# EEG_2.net
KiCad netlist of a schematic drawn in Altium Designer
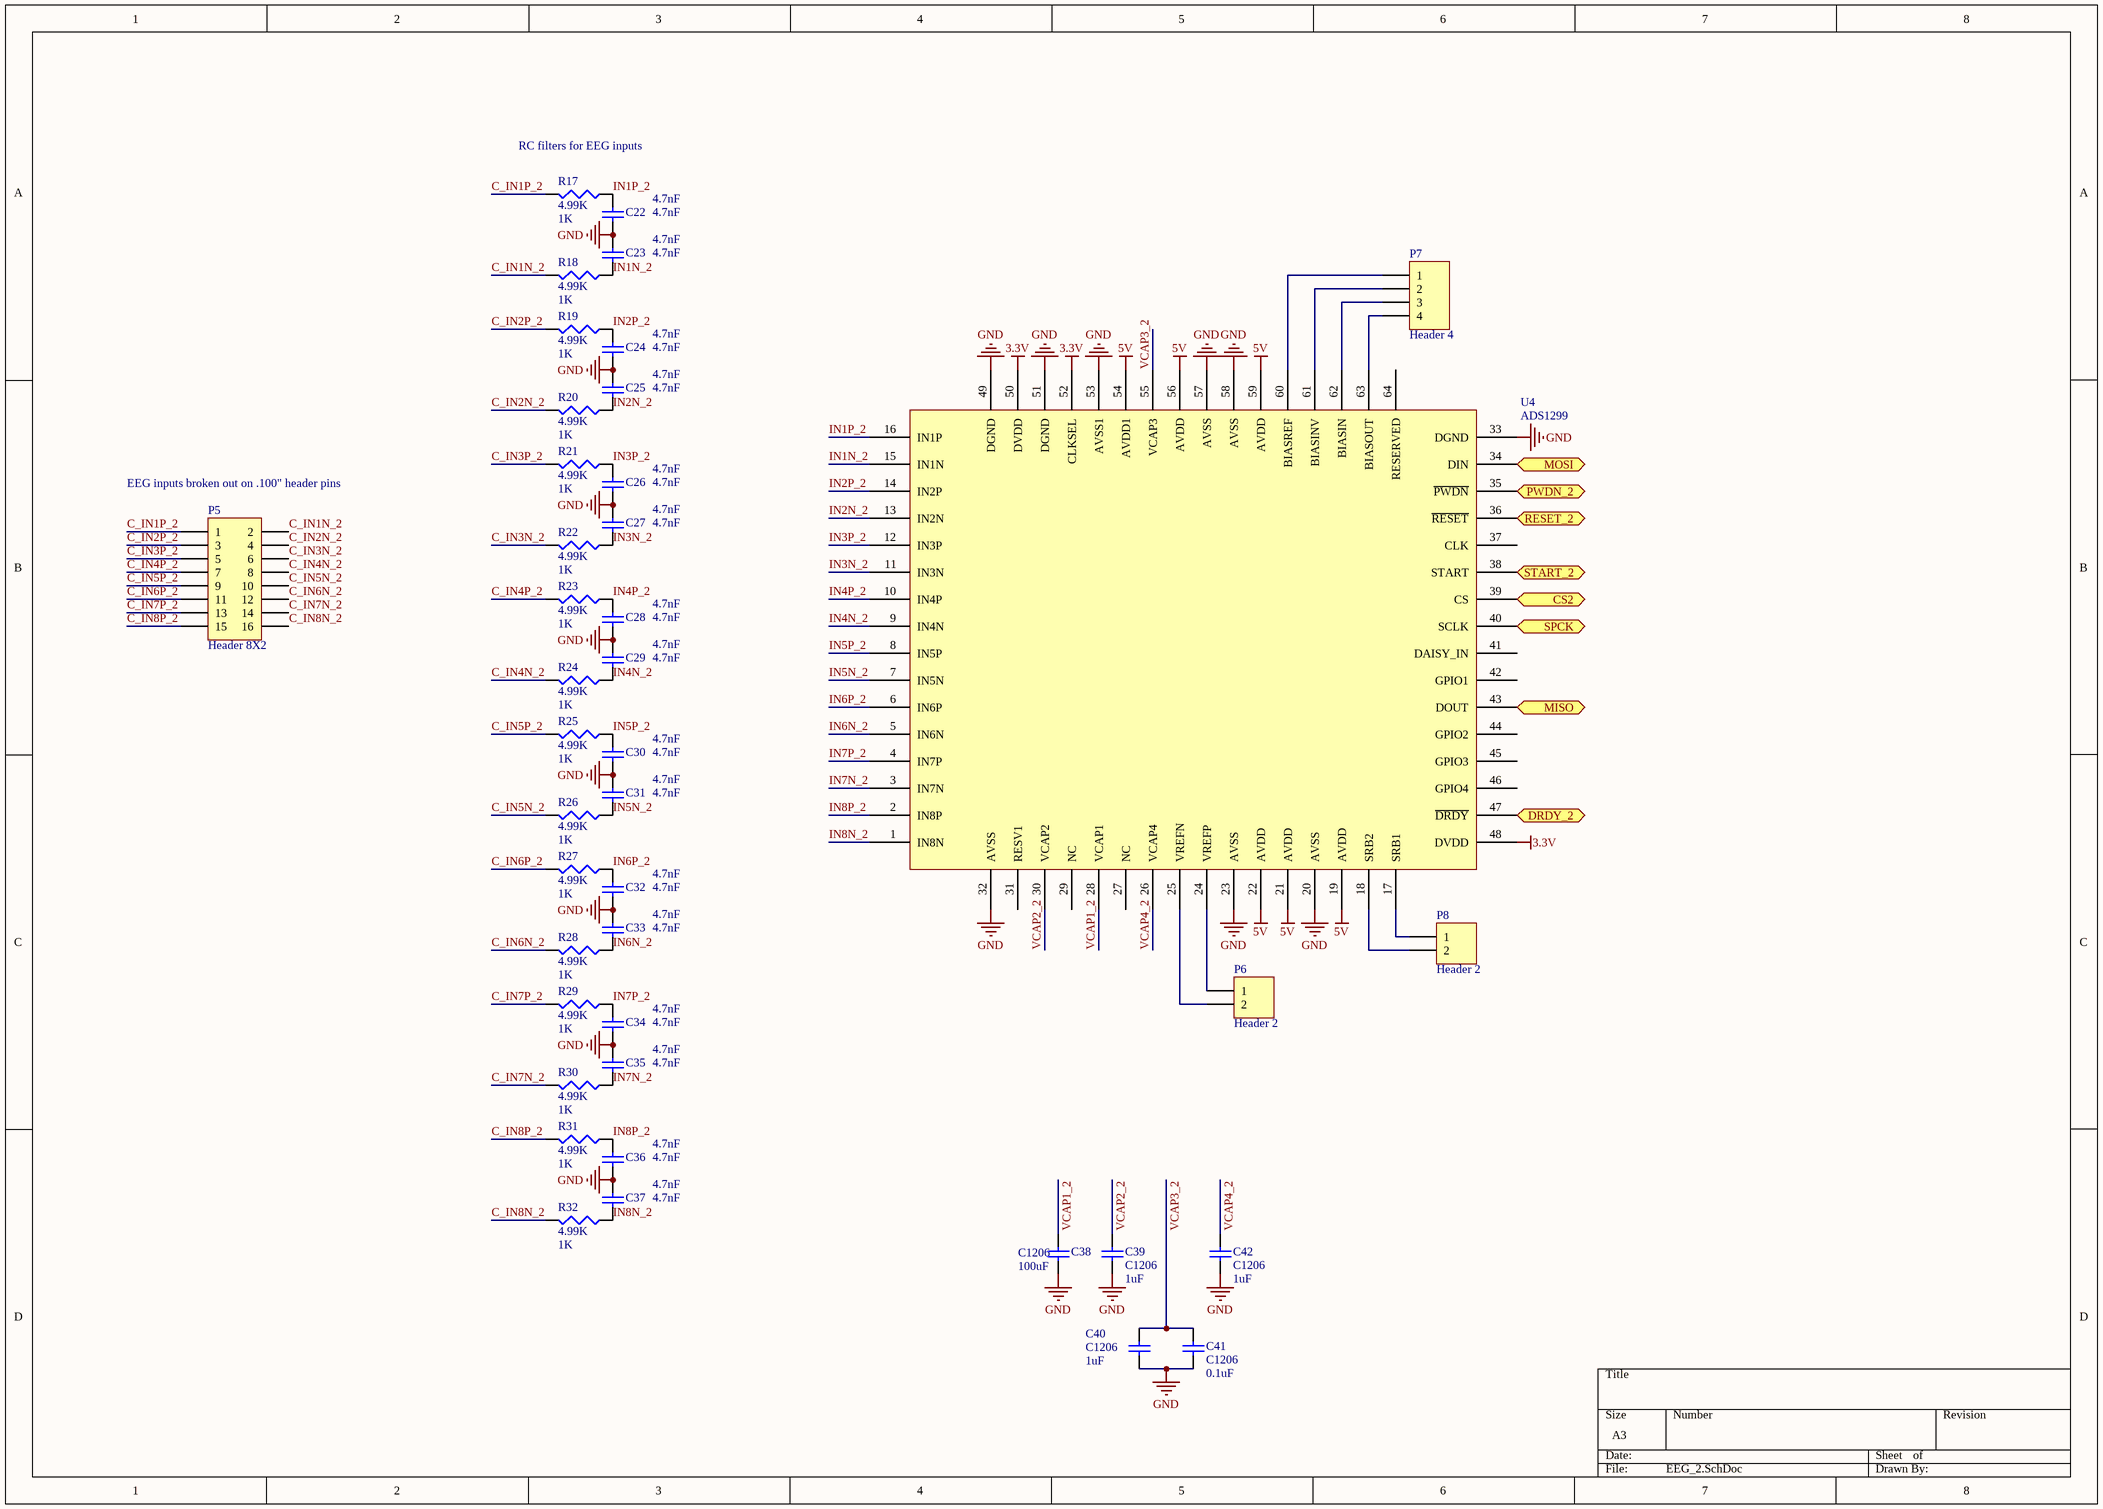
[diagram p0: EEG_2.SchDoc]

(export (version "E")
  (design (tool "Eeschema 10.0.6"))
  (components
    (comp (ref "C22")
      (value "4.7nF")
      (footprint "1608[0603]")
      (description "Capacitor (Semiconductor SIM Model)")
      (fields (field (name "ALTIUM_VALUE") "4.7nF") (field (name "PUBLISHER") "Altium Limited"))
      (libsource (lib "Miscellaneous Devices") (part "Cap Semi"))
    )
    (comp (ref "C23")
      (value "4.7nF")
      (footprint "1608[0603]")
      (description "Capacitor (Semiconductor SIM Model)")
      (fields (field (name "ALTIUM_VALUE") "4.7nF") (field (name "PUBLISHER") "Altium Limited"))
      (libsource (lib "Miscellaneous Devices") (part "Cap Semi"))
    )
    (comp (ref "C24")
      (value "4.7nF")
      (footprint "1608[0603]")
      (description "Capacitor (Semiconductor SIM Model)")
      (fields (field (name "ALTIUM_VALUE") "4.7nF") (field (name "PUBLISHER") "Altium Limited"))
      (libsource (lib "Miscellaneous Devices") (part "Cap Semi"))
    )
    (comp (ref "C25")
      (value "4.7nF")
      (footprint "1608[0603]")
      (description "Capacitor (Semiconductor SIM Model)")
      (fields (field (name "ALTIUM_VALUE") "4.7nF") (field (name "PUBLISHER") "Altium Limited"))
      (libsource (lib "Miscellaneous Devices") (part "Cap Semi"))
    )
    (comp (ref "C26")
      (value "4.7nF")
      (footprint "1608[0603]")
      (description "Capacitor (Semiconductor SIM Model)")
      (fields (field (name "ALTIUM_VALUE") "4.7nF") (field (name "PUBLISHER") "Altium Limited"))
      (libsource (lib "Miscellaneous Devices") (part "Cap Semi"))
    )
    (comp (ref "C27")
      (value "4.7nF")
      (footprint "1608[0603]")
      (description "Capacitor (Semiconductor SIM Model)")
      (fields (field (name "ALTIUM_VALUE") "4.7nF") (field (name "PUBLISHER") "Altium Limited"))
      (libsource (lib "Miscellaneous Devices") (part "Cap Semi"))
    )
    (comp (ref "C28")
      (value "4.7nF")
      (footprint "1608[0603]")
      (description "Capacitor (Semiconductor SIM Model)")
      (fields (field (name "ALTIUM_VALUE") "4.7nF") (field (name "PUBLISHER") "Altium Limited"))
      (libsource (lib "Miscellaneous Devices") (part "Cap Semi"))
    )
    (comp (ref "C29")
      (value "4.7nF")
      (footprint "1608[0603]")
      (description "Capacitor (Semiconductor SIM Model)")
      (fields (field (name "ALTIUM_VALUE") "4.7nF") (field (name "PUBLISHER") "Altium Limited"))
      (libsource (lib "Miscellaneous Devices") (part "Cap Semi"))
    )
    (comp (ref "C30")
      (value "4.7nF")
      (footprint "1608[0603]")
      (description "Capacitor (Semiconductor SIM Model)")
      (fields (field (name "ALTIUM_VALUE") "4.7nF") (field (name "PUBLISHER") "Altium Limited"))
      (libsource (lib "Miscellaneous Devices") (part "Cap Semi"))
    )
    (comp (ref "C31")
      (value "4.7nF")
      (footprint "1608[0603]")
      (description "Capacitor (Semiconductor SIM Model)")
      (fields (field (name "ALTIUM_VALUE") "4.7nF") (field (name "PUBLISHER") "Altium Limited"))
      (libsource (lib "Miscellaneous Devices") (part "Cap Semi"))
    )
    (comp (ref "C32")
      (value "4.7nF")
      (footprint "1608[0603]")
      (description "Capacitor (Semiconductor SIM Model)")
      (fields (field (name "ALTIUM_VALUE") "4.7nF") (field (name "PUBLISHER") "Altium Limited"))
      (libsource (lib "Miscellaneous Devices") (part "Cap Semi"))
    )
    (comp (ref "C33")
      (value "4.7nF")
      (footprint "1608[0603]")
      (description "Capacitor (Semiconductor SIM Model)")
      (fields (field (name "ALTIUM_VALUE") "4.7nF") (field (name "PUBLISHER") "Altium Limited"))
      (libsource (lib "Miscellaneous Devices") (part "Cap Semi"))
    )
    (comp (ref "C34")
      (value "4.7nF")
      (footprint "1608[0603]")
      (description "Capacitor (Semiconductor SIM Model)")
      (fields (field (name "ALTIUM_VALUE") "4.7nF") (field (name "PUBLISHER") "Altium Limited"))
      (libsource (lib "Miscellaneous Devices") (part "Cap Semi"))
    )
    (comp (ref "C35")
      (value "4.7nF")
      (footprint "1608[0603]")
      (description "Capacitor (Semiconductor SIM Model)")
      (fields (field (name "ALTIUM_VALUE") "4.7nF") (field (name "PUBLISHER") "Altium Limited"))
      (libsource (lib "Miscellaneous Devices") (part "Cap Semi"))
    )
    (comp (ref "C36")
      (value "4.7nF")
      (footprint "1608[0603]")
      (description "Capacitor (Semiconductor SIM Model)")
      (fields (field (name "ALTIUM_VALUE") "4.7nF") (field (name "PUBLISHER") "Altium Limited"))
      (libsource (lib "Miscellaneous Devices") (part "Cap Semi"))
    )
    (comp (ref "C37")
      (value "4.7nF")
      (footprint "1608[0603]")
      (description "Capacitor (Semiconductor SIM Model)")
      (fields (field (name "ALTIUM_VALUE") "4.7nF") (field (name "PUBLISHER") "Altium Limited"))
      (libsource (lib "Miscellaneous Devices") (part "Cap Semi"))
    )
    (comp (ref "C38")
      (value "C1206")
      (footprint "1608[0603]")
      (description "Capacitor (Semiconductor SIM Model)")
      (fields (field (name "ALTIUM_VALUE") "100uF") (field (name "PUBLISHER") "Altium Limited"))
      (libsource (lib "Miscellaneous Devices") (part "Cap Semi"))
    )
    (comp (ref "C39")
      (value "C1206")
      (footprint "1608[0603]")
      (description "Capacitor (Semiconductor SIM Model)")
      (fields (field (name "ALTIUM_VALUE") "1uF") (field (name "PUBLISHER") "Altium Limited"))
      (libsource (lib "Miscellaneous Devices") (part "Cap Semi"))
    )
    (comp (ref "C40")
      (value "C1206")
      (footprint "1608[0603]")
      (description "Capacitor (Semiconductor SIM Model)")
      (fields (field (name "ALTIUM_VALUE") "1uF") (field (name "PUBLISHER") "Altium Limited"))
      (libsource (lib "Miscellaneous Devices") (part "Cap Semi"))
    )
    (comp (ref "C41")
      (value "C1206")
      (footprint "1608[0603]")
      (description "Capacitor (Semiconductor SIM Model)")
      (fields (field (name "ALTIUM_VALUE") "0.1uF") (field (name "PUBLISHER") "Altium Limited"))
      (libsource (lib "Miscellaneous Devices") (part "Cap Semi"))
    )
    (comp (ref "C42")
      (value "C1206")
      (footprint "1608[0603]")
      (description "Capacitor (Semiconductor SIM Model)")
      (fields (field (name "ALTIUM_VALUE") "1uF") (field (name "PUBLISHER") "Altium Limited"))
      (libsource (lib "Miscellaneous Devices") (part "Cap Semi"))
    )
    (comp (ref "P5")
      (value "Header 8X2")
      (footprint "HDR2X8")
      (description "Header, 8-Pin, Dual row")
      (fields (field (name "PUBLISHER") "Altium Limited"))
      (libsource (lib "Miscellaneous Connectors") (part "Header 8X2"))
    )
    (comp (ref "P6")
      (value "Header 2")
      (footprint "HDR1X2")
      (description "Header, 2-Pin")
      (fields (field (name "PUBLISHER") "Altium Limited"))
      (libsource (lib "Miscellaneous Connectors") (part "Header 2"))
    )
    (comp (ref "P7")
      (value "Header 4")
      (footprint "HDR1X4")
      (description "Header, 4-Pin")
      (fields (field (name "PUBLISHER") "Altium Limited"))
      (libsource (lib "Miscellaneous Connectors") (part "Header 4"))
    )
    (comp (ref "P8")
      (value "Header 2")
      (footprint "HDR1X2")
      (description "Header, 2-Pin")
      (fields (field (name "PUBLISHER") "Altium Limited"))
      (libsource (lib "Miscellaneous Connectors") (part "Header 2"))
    )
    (comp (ref "R17")
      (value "4.99K")
      (footprint "1608[0603]")
      (description "Resistor")
      (fields (field (name "ALTIUM_VALUE") "1K") (field (name "PUBLISHER") "Altium Limited"))
      (libsource (lib "Miscellaneous Devices") (part "Res3"))
    )
    (comp (ref "R18")
      (value "4.99K")
      (footprint "1608[0603]")
      (description "Resistor")
      (fields (field (name "ALTIUM_VALUE") "1K") (field (name "PUBLISHER") "Altium Limited"))
      (libsource (lib "Miscellaneous Devices") (part "Res3"))
    )
    (comp (ref "R19")
      (value "4.99K")
      (footprint "1608[0603]")
      (description "Resistor")
      (fields (field (name "ALTIUM_VALUE") "1K") (field (name "PUBLISHER") "Altium Limited"))
      (libsource (lib "Miscellaneous Devices") (part "Res3"))
    )
    (comp (ref "R20")
      (value "4.99K")
      (footprint "1608[0603]")
      (description "Resistor")
      (fields (field (name "ALTIUM_VALUE") "1K") (field (name "PUBLISHER") "Altium Limited"))
      (libsource (lib "Miscellaneous Devices") (part "Res3"))
    )
    (comp (ref "R21")
      (value "4.99K")
      (footprint "1608[0603]")
      (description "Resistor")
      (fields (field (name "ALTIUM_VALUE") "1K") (field (name "PUBLISHER") "Altium Limited"))
      (libsource (lib "Miscellaneous Devices") (part "Res3"))
    )
    (comp (ref "R22")
      (value "4.99K")
      (footprint "1608[0603]")
      (description "Resistor")
      (fields (field (name "ALTIUM_VALUE") "1K") (field (name "PUBLISHER") "Altium Limited"))
      (libsource (lib "Miscellaneous Devices") (part "Res3"))
    )
    (comp (ref "R23")
      (value "4.99K")
      (footprint "1608[0603]")
      (description "Resistor")
      (fields (field (name "ALTIUM_VALUE") "1K") (field (name "PUBLISHER") "Altium Limited"))
      (libsource (lib "Miscellaneous Devices") (part "Res3"))
    )
    (comp (ref "R24")
      (value "4.99K")
      (footprint "1608[0603]")
      (description "Resistor")
      (fields (field (name "ALTIUM_VALUE") "1K") (field (name "PUBLISHER") "Altium Limited"))
      (libsource (lib "Miscellaneous Devices") (part "Res3"))
    )
    (comp (ref "R25")
      (value "4.99K")
      (footprint "1608[0603]")
      (description "Resistor")
      (fields (field (name "ALTIUM_VALUE") "1K") (field (name "PUBLISHER") "Altium Limited"))
      (libsource (lib "Miscellaneous Devices") (part "Res3"))
    )
    (comp (ref "R26")
      (value "4.99K")
      (footprint "1608[0603]")
      (description "Resistor")
      (fields (field (name "ALTIUM_VALUE") "1K") (field (name "PUBLISHER") "Altium Limited"))
      (libsource (lib "Miscellaneous Devices") (part "Res3"))
    )
    (comp (ref "R27")
      (value "4.99K")
      (footprint "1608[0603]")
      (description "Resistor")
      (fields (field (name "ALTIUM_VALUE") "1K") (field (name "PUBLISHER") "Altium Limited"))
      (libsource (lib "Miscellaneous Devices") (part "Res3"))
    )
    (comp (ref "R28")
      (value "4.99K")
      (footprint "1608[0603]")
      (description "Resistor")
      (fields (field (name "ALTIUM_VALUE") "1K") (field (name "PUBLISHER") "Altium Limited"))
      (libsource (lib "Miscellaneous Devices") (part "Res3"))
    )
    (comp (ref "R29")
      (value "4.99K")
      (footprint "1608[0603]")
      (description "Resistor")
      (fields (field (name "ALTIUM_VALUE") "1K") (field (name "PUBLISHER") "Altium Limited"))
      (libsource (lib "Miscellaneous Devices") (part "Res3"))
    )
    (comp (ref "R30")
      (value "4.99K")
      (footprint "1608[0603]")
      (description "Resistor")
      (fields (field (name "ALTIUM_VALUE") "1K") (field (name "PUBLISHER") "Altium Limited"))
      (libsource (lib "Miscellaneous Devices") (part "Res3"))
    )
    (comp (ref "R31")
      (value "4.99K")
      (footprint "1608[0603]")
      (description "Resistor")
      (fields (field (name "ALTIUM_VALUE") "1K") (field (name "PUBLISHER") "Altium Limited"))
      (libsource (lib "Miscellaneous Devices") (part "Res3"))
    )
    (comp (ref "R32")
      (value "4.99K")
      (footprint "1608[0603]")
      (description "Resistor")
      (fields (field (name "ALTIUM_VALUE") "1K") (field (name "PUBLISHER") "Altium Limited"))
      (libsource (lib "Miscellaneous Devices") (part "Res3"))
    )
    (comp (ref "U4")
      (value "ADS1299")
      (footprint "ADS1299 Plastic QFP")
      (libsource (lib "ADS1299") (part "ADS1299"))
    )
  )
  (nets
    (net (code "1") (name "/CS2") (class "Default")
      (node (ref "U4") (pin "39") (pinfunction "CS_39") (pintype "passive"))
    )
    (net (code "2") (name "/C_IN1N_2") (class "Default")
      (node (ref "P5") (pin "2") (pinfunction "2_2") (pintype "passive"))
      (node (ref "R18") (pin "2") (pinfunction "2_2") (pintype "passive"))
    )
    (net (code "3") (name "/C_IN1P_2") (class "Default")
      (node (ref "P5") (pin "1") (pinfunction "1_1") (pintype "passive"))
      (node (ref "R17") (pin "2") (pinfunction "2_2") (pintype "passive"))
    )
    (net (code "4") (name "/C_IN2N_2") (class "Default")
      (node (ref "P5") (pin "4") (pinfunction "4_4") (pintype "passive"))
      (node (ref "R20") (pin "2") (pinfunction "2_2") (pintype "passive"))
    )
    (net (code "5") (name "/C_IN2P_2") (class "Default")
      (node (ref "P5") (pin "3") (pinfunction "3_3") (pintype "passive"))
      (node (ref "R19") (pin "2") (pinfunction "2_2") (pintype "passive"))
    )
    (net (code "6") (name "/C_IN3N_2") (class "Default")
      (node (ref "P5") (pin "6") (pinfunction "6_6") (pintype "passive"))
      (node (ref "R22") (pin "2") (pinfunction "2_2") (pintype "passive"))
    )
    (net (code "7") (name "/C_IN3P_2") (class "Default")
      (node (ref "P5") (pin "5") (pinfunction "5_5") (pintype "passive"))
      (node (ref "R21") (pin "2") (pinfunction "2_2") (pintype "passive"))
    )
    (net (code "8") (name "/C_IN4N_2") (class "Default")
      (node (ref "P5") (pin "8") (pinfunction "8_8") (pintype "passive"))
      (node (ref "R24") (pin "2") (pinfunction "2_2") (pintype "passive"))
    )
    (net (code "9") (name "/C_IN4P_2") (class "Default")
      (node (ref "P5") (pin "7") (pinfunction "7_7") (pintype "passive"))
      (node (ref "R23") (pin "2") (pinfunction "2_2") (pintype "passive"))
    )
    (net (code "10") (name "/C_IN5N_2") (class "Default")
      (node (ref "P5") (pin "10") (pinfunction "10_10") (pintype "passive"))
      (node (ref "R26") (pin "2") (pinfunction "2_2") (pintype "passive"))
    )
    (net (code "11") (name "/C_IN5P_2") (class "Default")
      (node (ref "P5") (pin "9") (pinfunction "9_9") (pintype "passive"))
      (node (ref "R25") (pin "2") (pinfunction "2_2") (pintype "passive"))
    )
    (net (code "12") (name "/C_IN6N_2") (class "Default")
      (node (ref "P5") (pin "12") (pinfunction "12_12") (pintype "passive"))
      (node (ref "R28") (pin "2") (pinfunction "2_2") (pintype "passive"))
    )
    (net (code "13") (name "/C_IN6P_2") (class "Default")
      (node (ref "P5") (pin "11") (pinfunction "11_11") (pintype "passive"))
      (node (ref "R27") (pin "2") (pinfunction "2_2") (pintype "passive"))
    )
    (net (code "14") (name "/C_IN7N_2") (class "Default")
      (node (ref "P5") (pin "14") (pinfunction "14_14") (pintype "passive"))
      (node (ref "R30") (pin "2") (pinfunction "2_2") (pintype "passive"))
    )
    (net (code "15") (name "/C_IN7P_2") (class "Default")
      (node (ref "P5") (pin "13") (pinfunction "13_13") (pintype "passive"))
      (node (ref "R29") (pin "2") (pinfunction "2_2") (pintype "passive"))
    )
    (net (code "16") (name "/C_IN8N_2") (class "Default")
      (node (ref "P5") (pin "16") (pinfunction "16_16") (pintype "passive"))
      (node (ref "R32") (pin "2") (pinfunction "2_2") (pintype "passive"))
    )
    (net (code "17") (name "/C_IN8P_2") (class "Default")
      (node (ref "P5") (pin "15") (pinfunction "15_15") (pintype "passive"))
      (node (ref "R31") (pin "2") (pinfunction "2_2") (pintype "passive"))
    )
    (net (code "18") (name "/DRDY_2") (class "Default")
      (node (ref "U4") (pin "47") (pinfunction "~{DRDY}_47") (pintype "passive"))
    )
    (net (code "19") (name "/IN1N_2") (class "Default")
      (node (ref "C23") (pin "1") (pinfunction "1_1") (pintype "passive"))
      (node (ref "R18") (pin "1") (pinfunction "1_1") (pintype "passive"))
      (node (ref "U4") (pin "15") (pinfunction "IN1N_15") (pintype "passive"))
    )
    (net (code "20") (name "/IN1P_2") (class "Default")
      (node (ref "C22") (pin "2") (pinfunction "2_2") (pintype "passive"))
      (node (ref "R17") (pin "1") (pinfunction "1_1") (pintype "passive"))
      (node (ref "U4") (pin "16") (pinfunction "IN1P_16") (pintype "passive"))
    )
    (net (code "21") (name "/IN2N_2") (class "Default")
      (node (ref "C25") (pin "1") (pinfunction "1_1") (pintype "passive"))
      (node (ref "R20") (pin "1") (pinfunction "1_1") (pintype "passive"))
      (node (ref "U4") (pin "13") (pinfunction "IN2N_13") (pintype "passive"))
    )
    (net (code "22") (name "/IN2P_2") (class "Default")
      (node (ref "C24") (pin "2") (pinfunction "2_2") (pintype "passive"))
      (node (ref "R19") (pin "1") (pinfunction "1_1") (pintype "passive"))
      (node (ref "U4") (pin "14") (pinfunction "IN2P_14") (pintype "passive"))
    )
    (net (code "23") (name "/IN3N_2") (class "Default")
      (node (ref "C27") (pin "1") (pinfunction "1_1") (pintype "passive"))
      (node (ref "R22") (pin "1") (pinfunction "1_1") (pintype "passive"))
      (node (ref "U4") (pin "11") (pinfunction "IN3N_11") (pintype "passive"))
    )
    (net (code "24") (name "/IN3P_2") (class "Default")
      (node (ref "C26") (pin "2") (pinfunction "2_2") (pintype "passive"))
      (node (ref "R21") (pin "1") (pinfunction "1_1") (pintype "passive"))
      (node (ref "U4") (pin "12") (pinfunction "IN3P_12") (pintype "passive"))
    )
    (net (code "25") (name "/IN4N_2") (class "Default")
      (node (ref "C29") (pin "1") (pinfunction "1_1") (pintype "passive"))
      (node (ref "R24") (pin "1") (pinfunction "1_1") (pintype "passive"))
      (node (ref "U4") (pin "9") (pinfunction "IN4N_9") (pintype "passive"))
    )
    (net (code "26") (name "/IN4P_2") (class "Default")
      (node (ref "C28") (pin "2") (pinfunction "2_2") (pintype "passive"))
      (node (ref "R23") (pin "1") (pinfunction "1_1") (pintype "passive"))
      (node (ref "U4") (pin "10") (pinfunction "IN4P_10") (pintype "passive"))
    )
    (net (code "27") (name "/IN5N_2") (class "Default")
      (node (ref "C31") (pin "1") (pinfunction "1_1") (pintype "passive"))
      (node (ref "R26") (pin "1") (pinfunction "1_1") (pintype "passive"))
      (node (ref "U4") (pin "7") (pinfunction "IN5N_7") (pintype "passive"))
    )
    (net (code "28") (name "/IN5P_2") (class "Default")
      (node (ref "C30") (pin "2") (pinfunction "2_2") (pintype "passive"))
      (node (ref "R25") (pin "1") (pinfunction "1_1") (pintype "passive"))
      (node (ref "U4") (pin "8") (pinfunction "IN5P_8") (pintype "passive"))
    )
    (net (code "29") (name "/IN6N_2") (class "Default")
      (node (ref "C33") (pin "1") (pinfunction "1_1") (pintype "passive"))
      (node (ref "R28") (pin "1") (pinfunction "1_1") (pintype "passive"))
      (node (ref "U4") (pin "5") (pinfunction "IN6N_5") (pintype "passive"))
    )
    (net (code "30") (name "/IN6P_2") (class "Default")
      (node (ref "C32") (pin "2") (pinfunction "2_2") (pintype "passive"))
      (node (ref "R27") (pin "1") (pinfunction "1_1") (pintype "passive"))
      (node (ref "U4") (pin "6") (pinfunction "IN6P_6") (pintype "passive"))
    )
    (net (code "31") (name "/IN7N_2") (class "Default")
      (node (ref "C35") (pin "1") (pinfunction "1_1") (pintype "passive"))
      (node (ref "R30") (pin "1") (pinfunction "1_1") (pintype "passive"))
      (node (ref "U4") (pin "3") (pinfunction "IN7N_3") (pintype "passive"))
    )
    (net (code "32") (name "/IN7P_2") (class "Default")
      (node (ref "C34") (pin "2") (pinfunction "2_2") (pintype "passive"))
      (node (ref "R29") (pin "1") (pinfunction "1_1") (pintype "passive"))
      (node (ref "U4") (pin "4") (pinfunction "IN7P_4") (pintype "passive"))
    )
    (net (code "33") (name "/IN8N_2") (class "Default")
      (node (ref "C37") (pin "1") (pinfunction "1_1") (pintype "passive"))
      (node (ref "R32") (pin "1") (pinfunction "1_1") (pintype "passive"))
      (node (ref "U4") (pin "1") (pinfunction "IN8N_1") (pintype "passive"))
    )
    (net (code "34") (name "/IN8P_2") (class "Default")
      (node (ref "C36") (pin "2") (pinfunction "2_2") (pintype "passive"))
      (node (ref "R31") (pin "1") (pinfunction "1_1") (pintype "passive"))
      (node (ref "U4") (pin "2") (pinfunction "IN8P_2") (pintype "passive"))
    )
    (net (code "35") (name "/MISO") (class "Default")
      (node (ref "U4") (pin "43") (pinfunction "DOUT_43") (pintype "passive"))
    )
    (net (code "36") (name "/MOSI") (class "Default")
      (node (ref "U4") (pin "34") (pinfunction "DIN_34") (pintype "passive"))
    )
    (net (code "37") (name "/PWDN_2") (class "Default")
      (node (ref "U4") (pin "35") (pinfunction "~{PWDN}_35") (pintype "passive"))
    )
    (net (code "38") (name "/RESET_2") (class "Default")
      (node (ref "U4") (pin "36") (pinfunction "~{RESET}_36") (pintype "passive"))
    )
    (net (code "39") (name "/SPCK") (class "Default")
      (node (ref "U4") (pin "40") (pinfunction "SCLK_40") (pintype "passive"))
    )
    (net (code "40") (name "/START_2") (class "Default")
      (node (ref "U4") (pin "38") (pinfunction "START_38") (pintype "passive"))
    )
    (net (code "41") (name "/VCAP1_2") (class "Default")
      (node (ref "C38") (pin "1") (pinfunction "1_1") (pintype "passive"))
      (node (ref "U4") (pin "28") (pinfunction "VCAP1_28") (pintype "passive"))
    )
    (net (code "42") (name "/VCAP2_2") (class "Default")
      (node (ref "C39") (pin "2") (pinfunction "2_2") (pintype "passive"))
      (node (ref "U4") (pin "30") (pinfunction "VCAP2_30") (pintype "passive"))
    )
    (net (code "43") (name "/VCAP3_2") (class "Default")
      (node (ref "C40") (pin "1") (pinfunction "1_1") (pintype "passive"))
      (node (ref "C41") (pin "2") (pinfunction "2_2") (pintype "passive"))
      (node (ref "U4") (pin "55") (pinfunction "VCAP3_55") (pintype "passive"))
    )
    (net (code "44") (name "/VCAP4_2") (class "Default")
      (node (ref "C42") (pin "2") (pinfunction "2_2") (pintype "passive"))
      (node (ref "U4") (pin "26") (pinfunction "VCAP4_26") (pintype "passive"))
    )
    (net (code "45") (name "3.3V") (class "Default")
      (node (ref "U4") (pin "48") (pinfunction "DVDD_48") (pintype "passive"))
      (node (ref "U4") (pin "50") (pinfunction "DVDD_50") (pintype "passive"))
      (node (ref "U4") (pin "52") (pinfunction "CLKSEL_52") (pintype "passive"))
    )
    (net (code "46") (name "5V") (class "Default")
      (node (ref "U4") (pin "19") (pinfunction "AVDD_19") (pintype "passive"))
      (node (ref "U4") (pin "21") (pinfunction "AVDD_21") (pintype "passive"))
      (node (ref "U4") (pin "22") (pinfunction "AVDD_22") (pintype "passive"))
      (node (ref "U4") (pin "54") (pinfunction "AVDD1_54") (pintype "passive"))
      (node (ref "U4") (pin "56") (pinfunction "AVDD_56") (pintype "passive"))
      (node (ref "U4") (pin "59") (pinfunction "AVDD_59") (pintype "passive"))
    )
    (net (code "47") (name "GND") (class "Default")
      (node (ref "C22") (pin "1") (pinfunction "1_1") (pintype "passive"))
      (node (ref "C23") (pin "2") (pinfunction "2_2") (pintype "passive"))
      (node (ref "C24") (pin "1") (pinfunction "1_1") (pintype "passive"))
      (node (ref "C25") (pin "2") (pinfunction "2_2") (pintype "passive"))
      (node (ref "C26") (pin "1") (pinfunction "1_1") (pintype "passive"))
      (node (ref "C27") (pin "2") (pinfunction "2_2") (pintype "passive"))
      (node (ref "C28") (pin "1") (pinfunction "1_1") (pintype "passive"))
      (node (ref "C29") (pin "2") (pinfunction "2_2") (pintype "passive"))
      (node (ref "C30") (pin "1") (pinfunction "1_1") (pintype "passive"))
      (node (ref "C31") (pin "2") (pinfunction "2_2") (pintype "passive"))
      (node (ref "C32") (pin "1") (pinfunction "1_1") (pintype "passive"))
      (node (ref "C33") (pin "2") (pinfunction "2_2") (pintype "passive"))
      (node (ref "C34") (pin "1") (pinfunction "1_1") (pintype "passive"))
      (node (ref "C35") (pin "2") (pinfunction "2_2") (pintype "passive"))
      (node (ref "C36") (pin "1") (pinfunction "1_1") (pintype "passive"))
      (node (ref "C37") (pin "2") (pinfunction "2_2") (pintype "passive"))
      (node (ref "C38") (pin "2") (pinfunction "2_2") (pintype "passive"))
      (node (ref "C39") (pin "1") (pinfunction "1_1") (pintype "passive"))
      (node (ref "C40") (pin "2") (pinfunction "2_2") (pintype "passive"))
      (node (ref "C41") (pin "1") (pinfunction "1_1") (pintype "passive"))
      (node (ref "C42") (pin "1") (pinfunction "1_1") (pintype "passive"))
      (node (ref "U4") (pin "20") (pinfunction "AVSS_20") (pintype "passive"))
      (node (ref "U4") (pin "23") (pinfunction "AVSS_23") (pintype "passive"))
      (node (ref "U4") (pin "32") (pinfunction "AVSS_32") (pintype "passive"))
      (node (ref "U4") (pin "33") (pinfunction "DGND_33") (pintype "passive"))
      (node (ref "U4") (pin "49") (pinfunction "DGND_49") (pintype "passive"))
      (node (ref "U4") (pin "51") (pinfunction "DGND_51") (pintype "passive"))
      (node (ref "U4") (pin "53") (pinfunction "AVSS1_53") (pintype "passive"))
      (node (ref "U4") (pin "57") (pinfunction "AVSS_57") (pintype "passive"))
      (node (ref "U4") (pin "58") (pinfunction "AVSS_58") (pintype "passive"))
    )
    (net (code "48") (name "Net-(U4-BIASIN)") (class "Default")
      (node (ref "P7") (pin "3") (pinfunction "3_3") (pintype "passive"))
      (node (ref "U4") (pin "62") (pinfunction "BIASIN_62") (pintype "passive"))
    )
    (net (code "49") (name "Net-(U4-BIASINV)") (class "Default")
      (node (ref "P7") (pin "2") (pinfunction "2_2") (pintype "passive"))
      (node (ref "U4") (pin "61") (pinfunction "BIASINV_61") (pintype "passive"))
    )
    (net (code "50") (name "Net-(U4-BIASOUT)") (class "Default")
      (node (ref "P7") (pin "4") (pinfunction "4_4") (pintype "passive"))
      (node (ref "U4") (pin "63") (pinfunction "BIASOUT_63") (pintype "passive"))
    )
    (net (code "51") (name "Net-(U4-BIASREF)") (class "Default")
      (node (ref "P7") (pin "1") (pinfunction "1_1") (pintype "passive"))
      (node (ref "U4") (pin "60") (pinfunction "BIASREF_60") (pintype "passive"))
    )
    (net (code "52") (name "Net-(U4-SRB1)") (class "Default")
      (node (ref "P8") (pin "1") (pinfunction "1_1") (pintype "passive"))
      (node (ref "U4") (pin "17") (pinfunction "SRB1_17") (pintype "passive"))
    )
    (net (code "53") (name "Net-(U4-SRB2)") (class "Default")
      (node (ref "P8") (pin "2") (pinfunction "2_2") (pintype "passive"))
      (node (ref "U4") (pin "18") (pinfunction "SRB2_18") (pintype "passive"))
    )
    (net (code "54") (name "Net-(U4-VREFN)") (class "Default")
      (node (ref "P6") (pin "2") (pinfunction "2_2") (pintype "passive"))
      (node (ref "U4") (pin "25") (pinfunction "VREFN_25") (pintype "passive"))
    )
    (net (code "55") (name "Net-(U4-VREFP)") (class "Default")
      (node (ref "P6") (pin "1") (pinfunction "1_1") (pintype "passive"))
      (node (ref "U4") (pin "24") (pinfunction "VREFP_24") (pintype "passive"))
    )
    (net (code "56") (name "unconnected-(U4-CLK-Pad37)") (class "Default")
      (node (ref "U4") (pin "37") (pinfunction "CLK_37") (pintype "passive"))
    )
    (net (code "57") (name "unconnected-(U4-DAISY_IN-Pad41)") (class "Default")
      (node (ref "U4") (pin "41") (pinfunction "DAISY_IN_41") (pintype "passive"))
    )
    (net (code "58") (name "unconnected-(U4-GPIO1-Pad42)") (class "Default")
      (node (ref "U4") (pin "42") (pinfunction "GPIO1_42") (pintype "passive"))
    )
    (net (code "59") (name "unconnected-(U4-GPIO2-Pad44)") (class "Default")
      (node (ref "U4") (pin "44") (pinfunction "GPIO2_44") (pintype "passive"))
    )
    (net (code "60") (name "unconnected-(U4-GPIO3-Pad45)") (class "Default")
      (node (ref "U4") (pin "45") (pinfunction "GPIO3_45") (pintype "passive"))
    )
    (net (code "61") (name "unconnected-(U4-GPIO4-Pad46)") (class "Default")
      (node (ref "U4") (pin "46") (pinfunction "GPIO4_46") (pintype "passive"))
    )
    (net (code "62") (name "unconnected-(U4-NC-Pad27)") (class "Default")
      (node (ref "U4") (pin "27") (pinfunction "NC_27") (pintype "passive"))
    )
    (net (code "63") (name "unconnected-(U4-NC-Pad29)") (class "Default")
      (node (ref "U4") (pin "29") (pinfunction "NC_29") (pintype "passive"))
    )
    (net (code "64") (name "unconnected-(U4-RESERVED-Pad64)") (class "Default")
      (node (ref "U4") (pin "64") (pinfunction "RESERVED_64") (pintype "passive"))
    )
    (net (code "65") (name "unconnected-(U4-RESV1-Pad31)") (class "Default")
      (node (ref "U4") (pin "31") (pinfunction "RESV1_31") (pintype "passive"))
    )
  )
)
